# 5_-_RS485-TRANSCEIVER.net
KiCad netlist of a schematic drawn in Altium Designer
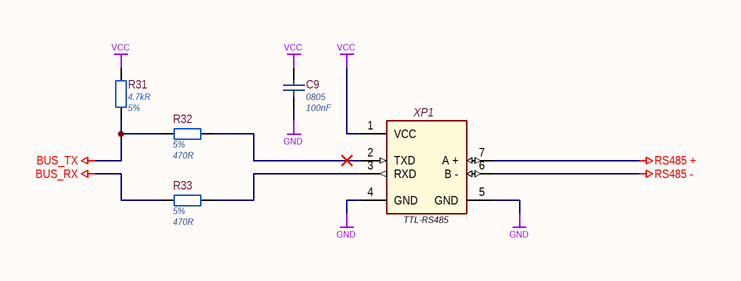
[diagram p0: [5] - RS485-TRANSCEIVER.SchDoc]

(export (version "E")
  (design (tool "Eeschema 10.0.6"))
  (components
    (comp (ref "C9")
      (value "AC0805KRX7R9BB104")
      (footprint "CH0805C")
      (description "0.10µF 50V Ceramic Capacitor X7R 0805 (2012 Metric) 0.079\" L x 0.049\" W (2.00mm x 1.25mm)")
      (fields
        (field (name "CASE/PACKAGE") "0805")
        (field (name "CAPACITANCE") "100nF")
        (field (name "TOLERANCE") "10%")
      )
      (libsource (lib "Chip Capacitors") (part "AC0805KRX7R9BB104"))
    )
    (comp (ref "R31")
      (value "RC0805JR-074K7L")
      (footprint "CH0805R")
      (description "RES SMD 4.7K OHM 5% 1/8W 0805")
      (fields (field (name "RESISTANCE") "4.7kR") (field (name "TOLERANCE") "5%"))
      (libsource (lib "Chip Resistors") (part "RC0805JR-074K7L"))
    )
    (comp (ref "R32")
      (value "RC0805JR-07470RL")
      (footprint "CH0805R")
      (description "RES SMD 470 OHM 5% 1/8W 0805")
      (fields (field (name "TOLERANCE") "5%") (field (name "RESISTANCE") "470R"))
      (libsource (lib "Chip Resistors") (part "RC0805JR-07470RL"))
    )
    (comp (ref "R33")
      (value "RC0805JR-07470RL")
      (footprint "CH0805R")
      (description "RES SMD 470 OHM 5% 1/8W 0805")
      (fields (field (name "TOLERANCE") "5%") (field (name "RESISTANCE") "470R"))
      (libsource (lib "Chip Resistors") (part "RC0805JR-07470RL"))
    )
    (comp (ref "XP1")
      (value "TTL-RS485")
      (footprint "TTL-RS485")
      (description "UART TTL to RS485 Two-way Converter Module")
      (libsource (lib "Modules") (part "TTL-RS485"))
    )
  )
  (nets
    (net (code "1") (name "BUS_RX") (class "Default")
      (node (ref "R33") (pin "1") (pinfunction "1_1") (pintype "passive"))
    )
    (net (code "2") (name "BUS_TX") (class "Default")
      (node (ref "R31") (pin "2") (pinfunction "2_2") (pintype "passive"))
      (node (ref "R32") (pin "1") (pinfunction "1_1") (pintype "passive"))
    )
    (net (code "3") (name "GND") (class "Default")
      (node (ref "C9") (pin "2") (pinfunction "2_2") (pintype "passive"))
      (node (ref "XP1") (pin "4") (pinfunction "GND_4") (pintype "power_in"))
      (node (ref "XP1") (pin "5") (pinfunction "GND_5") (pintype "power_in"))
    )
    (net (code "4") (name "Net-(XP1-RXD)") (class "Default")
      (node (ref "R33") (pin "2") (pinfunction "2_2") (pintype "passive"))
      (node (ref "XP1") (pin "3") (pinfunction "RXD_3") (pintype "output"))
    )
    (net (code "5") (name "Net-(XP1-TXD)") (class "Default")
      (node (ref "R32") (pin "2") (pinfunction "2_2") (pintype "passive"))
      (node (ref "XP1") (pin "2") (pinfunction "TXD_2") (pintype "input"))
    )
    (net (code "6") (name "RS485 +") (class "Default")
      (node (ref "XP1") (pin "7") (pinfunction "A_+_7") (pintype "bidirectional"))
    )
    (net (code "7") (name "RS485 -") (class "Default")
      (node (ref "XP1") (pin "6") (pinfunction "B_-_6") (pintype "bidirectional"))
    )
    (net (code "8") (name "VCC") (class "Default")
      (node (ref "C9") (pin "1") (pinfunction "1_1") (pintype "passive"))
      (node (ref "R31") (pin "1") (pinfunction "1_1") (pintype "passive"))
      (node (ref "XP1") (pin "1") (pinfunction "VCC_1") (pintype "power_in"))
    )
  )
)
